# fedpower_mic841_reve.net
KiCad netlist of a schematic drawn in EAGLE
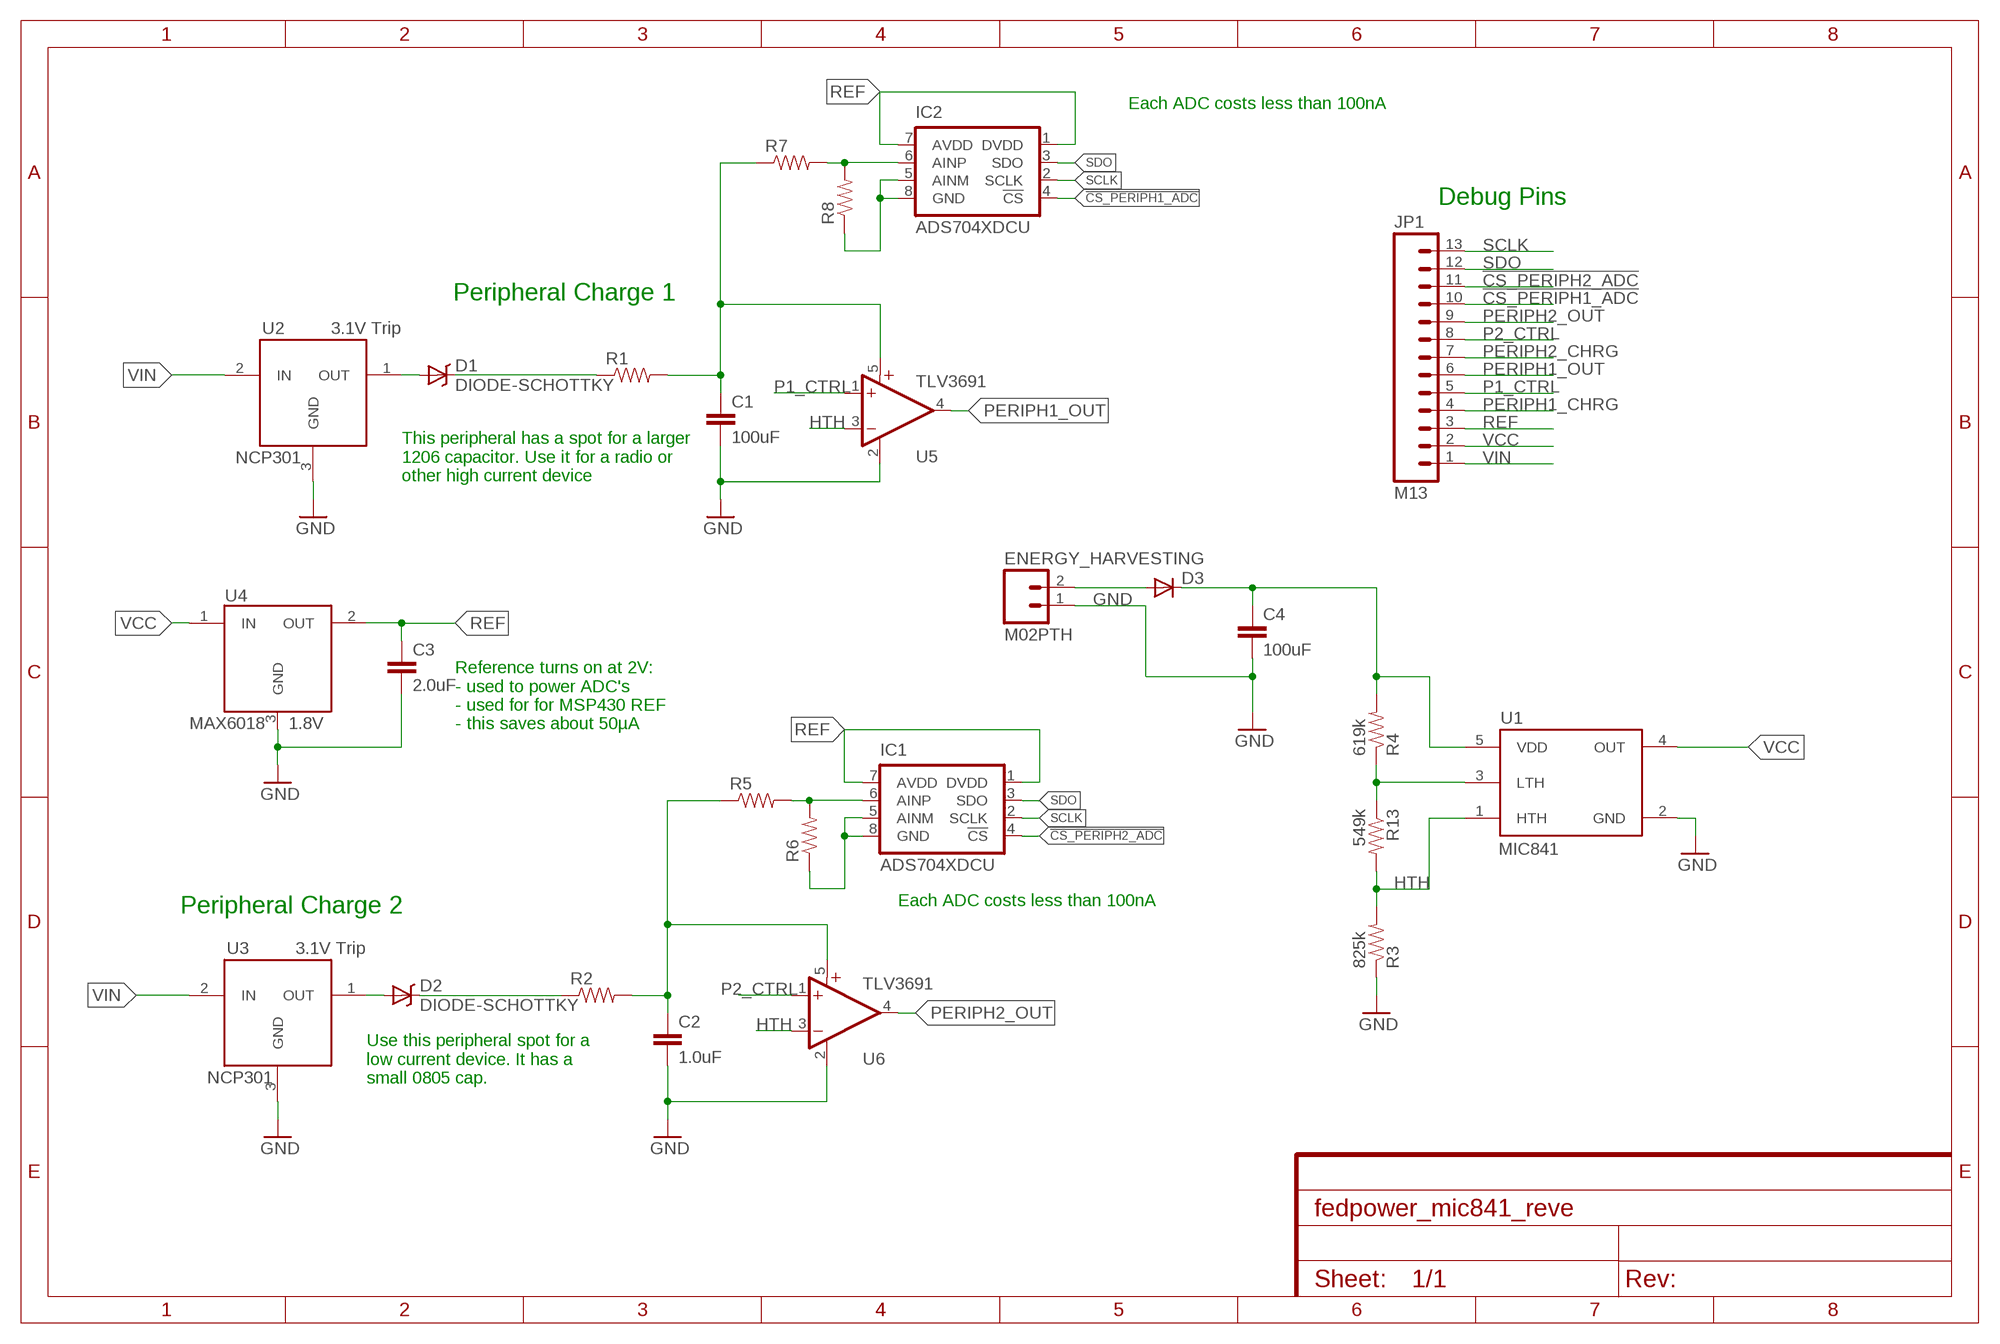
[diagram p0: schematic, sheet 1]

(export (version "E")
  (design (tool "Eeschema 10.0.6"))
  (components
    (comp (ref "C1")
      (value "100uF")
      (footprint "eagle-import:1206")
      (libsource (lib "eagle-import") (part "2.2UF50V10%(1206)"))
    )
    (comp (ref "C2")
      (value "1.0uF")
      (footprint "eagle-import:0805")
      (libsource (lib "eagle-import") (part "1.0UF-25V-+80/-20(0805)"))
    )
    (comp (ref "C3")
      (value "2.0uF")
      (footprint "eagle-import:0805")
      (libsource (lib "eagle-import") (part "1.0UF-25V-+80/-20(0805)"))
    )
    (comp (ref "C4")
      (value "100uF")
      (footprint "eagle-import:1206")
      (libsource (lib "eagle-import") (part "2.2UF-CERCAP-10009"))
    )
    (comp (ref "D1")
      (value "DIODE-SCHOTTKY")
      (footprint "eagle-import:SOD-323")
      (libsource (lib "eagle-import") (part "DIODE-SCHOTTKY"))
    )
    (comp (ref "D2")
      (value "DIODE-SCHOTTKY")
      (footprint "eagle-import:SOD-323")
      (libsource (lib "eagle-import") (part "DIODE-SCHOTTKY"))
    )
    (comp (ref "D3")
      (value "DIODESOD")
      (footprint "eagle-import:SOD-323")
      (libsource (lib "eagle-import") (part "DIODESOD"))
    )
    (comp (ref "ENERGY_HARVESTING")
      (value "M02PTH")
      (footprint "eagle-import:1X02")
      (libsource (lib "eagle-import") (part "M02PTH"))
    )
    (comp (ref "IC1")
      (value "ADS704XDCU")
      (footprint "eagle-import:DCU_(R-PDSO-G8)")
      (libsource (lib "eagle-import") (part "ADS704XDCU"))
    )
    (comp (ref "IC2")
      (value "ADS704XDCU")
      (footprint "eagle-import:DCU_(R-PDSO-G8)")
      (libsource (lib "eagle-import") (part "ADS704XDCU"))
    )
    (comp (ref "JP1")
      (value "M13")
      (footprint "eagle-import:1X13")
      (libsource (lib "eagle-import") (part "M13"))
    )
    (comp (ref "R1")
      (value "0.3OHM-1/8W-1%(0805)")
      (footprint "eagle-import:0805")
      (libsource (lib "eagle-import") (part "0.3OHM-1/8W-1%(0805)"))
    )
    (comp (ref "R2")
      (value "0.3OHM-1/8W-1%(0805)")
      (footprint "eagle-import:0805")
      (libsource (lib "eagle-import") (part "0.3OHM-1/8W-1%(0805)"))
    )
    (comp (ref "R3")
      (value "825k")
      (footprint "eagle-import:0805")
      (libsource (lib "eagle-import") (part "0.3OHM-1/8W-1%(0805)"))
    )
    (comp (ref "R4")
      (value "619k")
      (footprint "eagle-import:0805")
      (libsource (lib "eagle-import") (part "0.3OHM-1/8W-1%(0805)"))
    )
    (comp (ref "R5")
      (value "0.3OHM-1/8W-1%(0805)")
      (footprint "eagle-import:0805")
      (libsource (lib "eagle-import") (part "0.3OHM-1/8W-1%(0805)"))
    )
    (comp (ref "R6")
      (value "0.3OHM-1/8W-1%(0805)")
      (footprint "eagle-import:0805")
      (libsource (lib "eagle-import") (part "0.3OHM-1/8W-1%(0805)"))
    )
    (comp (ref "R7")
      (value "0.3OHM-1/8W-1%(0805)")
      (footprint "eagle-import:0805")
      (libsource (lib "eagle-import") (part "0.3OHM-1/8W-1%(0805)"))
    )
    (comp (ref "R8")
      (value "0.3OHM-1/8W-1%(0805)")
      (footprint "eagle-import:0805")
      (libsource (lib "eagle-import") (part "0.3OHM-1/8W-1%(0805)"))
    )
    (comp (ref "R13")
      (value "549k")
      (footprint "eagle-import:0805")
      (libsource (lib "eagle-import") (part "0.3OHM-1/8W-1%(0805)"))
    )
    (comp (ref "U1")
      (value "MIC841")
      (footprint "eagle-import:SC70-5")
      (libsource (lib "eagle-import") (part "MIC841"))
    )
    (comp (ref "U2")
      (value "3.1V Trip")
      (footprint "eagle-import:SOT-23-5_1PRIMARY")
      (libsource (lib "eagle-import") (part "NCP300{dblquote}"))
    )
    (comp (ref "U3")
      (value "3.1V Trip")
      (footprint "eagle-import:SOT-23-5_1PRIMARY")
      (libsource (lib "eagle-import") (part "NCP300{dblquote}"))
    )
    (comp (ref "U4")
      (value "1.8V")
      (footprint "eagle-import:SOT23-3")
      (libsource (lib "eagle-import") (part "MAX6018"))
    )
    (comp (ref "U5")
      (value "TLV3691")
      (footprint "eagle-import:SC70-5")
      (libsource (lib "eagle-import") (part "TLV3691"))
    )
    (comp (ref "U6")
      (value "TLV3691")
      (footprint "eagle-import:SC70-5")
      (libsource (lib "eagle-import") (part "TLV3691"))
    )
  )
  (nets
    (net (code "1") (name "/HTH") (class "Default")
      (node (ref "R13") (pin "2") (pinfunction "2_2") (pintype "passive"))
      (node (ref "R3") (pin "2") (pinfunction "2_2") (pintype "passive"))
      (node (ref "U1") (pin "1") (pinfunction "HTH_1") (pintype "bidirectional"))
      (node (ref "U5") (pin "3") (pinfunction "-IN_3") (pintype "input"))
      (node (ref "U6") (pin "3") (pinfunction "-IN_3") (pintype "input"))
    )
    (net (code "2") (name "/P1_CTRL") (class "Default")
      (node (ref "JP1") (pin "5") (pinfunction "5_5") (pintype "passive"))
      (node (ref "U5") (pin "1") (pinfunction "+IN_1") (pintype "input"))
    )
    (net (code "3") (name "/P2_CTRL") (class "Default")
      (node (ref "JP1") (pin "8") (pinfunction "8_8") (pintype "passive"))
      (node (ref "U6") (pin "1") (pinfunction "+IN_1") (pintype "input"))
    )
    (net (code "4") (name "/PERIPH1_CHRG") (class "Default")
      (node (ref "C1") (pin "1") (pinfunction "1_1") (pintype "passive"))
      (node (ref "JP1") (pin "4") (pinfunction "4_4") (pintype "passive"))
      (node (ref "R1") (pin "2") (pinfunction "2_2") (pintype "passive"))
      (node (ref "R7") (pin "1") (pinfunction "1_1") (pintype "passive"))
      (node (ref "U5") (pin "5") (pinfunction "V+_5") (pintype "power_in"))
    )
    (net (code "5") (name "/PERIPH2_CHRG") (class "Default")
      (node (ref "C2") (pin "1") (pinfunction "1_1") (pintype "passive"))
      (node (ref "JP1") (pin "7") (pinfunction "7_7") (pintype "passive"))
      (node (ref "R2") (pin "2") (pinfunction "2_2") (pintype "passive"))
      (node (ref "R5") (pin "1") (pinfunction "1_1") (pintype "passive"))
      (node (ref "U6") (pin "5") (pinfunction "V+_5") (pintype "power_in"))
    )
    (net (code "6") (name "/~{CS_PERIPH1_ADC}") (class "Default")
      (node (ref "IC2") (pin "4") (pinfunction "~{CS}_4") (pintype "input"))
      (node (ref "JP1") (pin "10") (pinfunction "10_10") (pintype "passive"))
    )
    (net (code "7") (name "/~{CS_PERIPH2_ADC}") (class "Default")
      (node (ref "IC1") (pin "4") (pinfunction "~{CS}_4") (pintype "input"))
      (node (ref "JP1") (pin "11") (pinfunction "11_11") (pintype "passive"))
    )
    (net (code "8") (name "GND") (class "Default")
      (node (ref "C1") (pin "2") (pinfunction "2_2") (pintype "passive"))
      (node (ref "C2") (pin "2") (pinfunction "2_2") (pintype "passive"))
      (node (ref "C3") (pin "2") (pinfunction "2_2") (pintype "passive"))
      (node (ref "C4") (pin "2") (pinfunction "2_2") (pintype "passive"))
      (node (ref "ENERGY_HARVESTING") (pin "1") (pinfunction "1_1") (pintype "passive"))
      (node (ref "R3") (pin "1") (pinfunction "1_1") (pintype "passive"))
      (node (ref "U1") (pin "2") (pinfunction "GND_2") (pintype "bidirectional"))
      (node (ref "U2") (pin "3") (pinfunction "GND_3") (pintype "bidirectional"))
      (node (ref "U3") (pin "3") (pinfunction "GND_3") (pintype "bidirectional"))
      (node (ref "U4") (pin "3") (pinfunction "GND_3") (pintype "bidirectional"))
      (node (ref "U5") (pin "2") (pinfunction "GND_2") (pintype "power_in"))
      (node (ref "U6") (pin "2") (pinfunction "GND_2") (pintype "power_in"))
    )
    (net (code "9") (name "Net-(D1-A)") (class "Default")
      (node (ref "D1") (pin "2") (pinfunction "A_2") (pintype "passive"))
      (node (ref "U2") (pin "1") (pinfunction "OUT_1") (pintype "bidirectional"))
    )
    (net (code "10") (name "Net-(D1-C)") (class "Default")
      (node (ref "D1") (pin "1") (pinfunction "C_1") (pintype "passive"))
      (node (ref "R1") (pin "1") (pinfunction "1_1") (pintype "passive"))
    )
    (net (code "11") (name "Net-(D2-A)") (class "Default")
      (node (ref "D2") (pin "2") (pinfunction "A_2") (pintype "passive"))
      (node (ref "U3") (pin "1") (pinfunction "OUT_1") (pintype "bidirectional"))
    )
    (net (code "12") (name "Net-(D2-C)") (class "Default")
      (node (ref "D2") (pin "1") (pinfunction "C_1") (pintype "passive"))
      (node (ref "R2") (pin "1") (pinfunction "1_1") (pintype "passive"))
    )
    (net (code "13") (name "Net-(D3-A)") (class "Default")
      (node (ref "D3") (pin "2") (pinfunction "A_2") (pintype "passive"))
      (node (ref "ENERGY_HARVESTING") (pin "2") (pinfunction "2_2") (pintype "passive"))
    )
    (net (code "14") (name "Net-(IC1-AINM)") (class "Default")
      (node (ref "IC1") (pin "5") (pinfunction "AINM_5") (pintype "input"))
      (node (ref "IC1") (pin "8") (pinfunction "GND_8") (pintype "power_in"))
      (node (ref "R6") (pin "1") (pinfunction "1_1") (pintype "passive"))
    )
    (net (code "15") (name "Net-(IC1-AINP)") (class "Default")
      (node (ref "IC1") (pin "6") (pinfunction "AINP_6") (pintype "input"))
      (node (ref "R5") (pin "2") (pinfunction "2_2") (pintype "passive"))
      (node (ref "R6") (pin "2") (pinfunction "2_2") (pintype "passive"))
    )
    (net (code "16") (name "Net-(IC2-AINM)") (class "Default")
      (node (ref "IC2") (pin "5") (pinfunction "AINM_5") (pintype "input"))
      (node (ref "IC2") (pin "8") (pinfunction "GND_8") (pintype "power_in"))
      (node (ref "R8") (pin "1") (pinfunction "1_1") (pintype "passive"))
    )
    (net (code "17") (name "Net-(IC2-AINP)") (class "Default")
      (node (ref "IC2") (pin "6") (pinfunction "AINP_6") (pintype "input"))
      (node (ref "R7") (pin "2") (pinfunction "2_2") (pintype "passive"))
      (node (ref "R8") (pin "2") (pinfunction "2_2") (pintype "passive"))
    )
    (net (code "18") (name "Net-(U1-LTH)") (class "Default")
      (node (ref "R13") (pin "1") (pinfunction "1_1") (pintype "passive"))
      (node (ref "R4") (pin "1") (pinfunction "1_1") (pintype "passive"))
      (node (ref "U1") (pin "3") (pinfunction "LTH_3") (pintype "bidirectional"))
    )
    (net (code "19") (name "PERIPH1_OUT") (class "Default")
      (node (ref "JP1") (pin "6") (pinfunction "6_6") (pintype "passive"))
      (node (ref "U5") (pin "4") (pinfunction "OUT_4") (pintype "output"))
    )
    (net (code "20") (name "PERIPH2_OUT") (class "Default")
      (node (ref "JP1") (pin "9") (pinfunction "9_9") (pintype "passive"))
      (node (ref "U6") (pin "4") (pinfunction "OUT_4") (pintype "output"))
    )
    (net (code "21") (name "REF") (class "Default")
      (node (ref "C3") (pin "1") (pinfunction "1_1") (pintype "passive"))
      (node (ref "IC1") (pin "1") (pinfunction "DVDD_1") (pintype "power_in"))
      (node (ref "IC1") (pin "7") (pinfunction "AVDD_7") (pintype "power_in"))
      (node (ref "IC2") (pin "1") (pinfunction "DVDD_1") (pintype "power_in"))
      (node (ref "IC2") (pin "7") (pinfunction "AVDD_7") (pintype "power_in"))
      (node (ref "JP1") (pin "3") (pinfunction "3_3") (pintype "passive"))
      (node (ref "U4") (pin "2") (pinfunction "OUT_2") (pintype "bidirectional"))
    )
    (net (code "22") (name "SCLK") (class "Default")
      (node (ref "IC1") (pin "2") (pinfunction "SCLK_2") (pintype "input"))
      (node (ref "IC2") (pin "2") (pinfunction "SCLK_2") (pintype "input"))
      (node (ref "JP1") (pin "13") (pinfunction "13_13") (pintype "passive"))
    )
    (net (code "23") (name "SDO") (class "Default")
      (node (ref "IC1") (pin "3") (pinfunction "SDO_3") (pintype "bidirectional"))
      (node (ref "IC2") (pin "3") (pinfunction "SDO_3") (pintype "bidirectional"))
      (node (ref "JP1") (pin "12") (pinfunction "12_12") (pintype "passive"))
    )
    (net (code "24") (name "VCC") (class "Default")
      (node (ref "JP1") (pin "2") (pinfunction "2_2") (pintype "passive"))
      (node (ref "U1") (pin "4") (pinfunction "OUT_4") (pintype "bidirectional"))
      (node (ref "U4") (pin "1") (pinfunction "IN_1") (pintype "bidirectional"))
    )
    (net (code "25") (name "VIN") (class "Default")
      (node (ref "C4") (pin "1") (pinfunction "1_1") (pintype "passive"))
      (node (ref "D3") (pin "1") (pinfunction "C_1") (pintype "passive"))
      (node (ref "JP1") (pin "1") (pinfunction "1_1") (pintype "passive"))
      (node (ref "R4") (pin "2") (pinfunction "2_2") (pintype "passive"))
      (node (ref "U1") (pin "5") (pinfunction "VDD_5") (pintype "bidirectional"))
      (node (ref "U2") (pin "2") (pinfunction "IN_2") (pintype "bidirectional"))
      (node (ref "U3") (pin "2") (pinfunction "IN_2") (pintype "bidirectional"))
    )
    (net (code "26") (name "unconnected-(U2-NC-Pad4)") (class "Default")
      (node (ref "U2") (pin "4") (pinfunction "NC_4") (pintype "no_connect"))
    )
    (net (code "27") (name "unconnected-(U2-NC-Pad5)") (class "Default")
      (node (ref "U2") (pin "5") (pinfunction "NC_5") (pintype "no_connect"))
    )
    (net (code "28") (name "unconnected-(U3-NC-Pad4)") (class "Default")
      (node (ref "U3") (pin "4") (pinfunction "NC_4") (pintype "no_connect"))
    )
    (net (code "29") (name "unconnected-(U3-NC-Pad5)") (class "Default")
      (node (ref "U3") (pin "5") (pinfunction "NC_5") (pintype "no_connect"))
    )
  )
)
